# LinuxBoard_v1_2.net
KiCad netlist of a schematic drawn in EAGLE
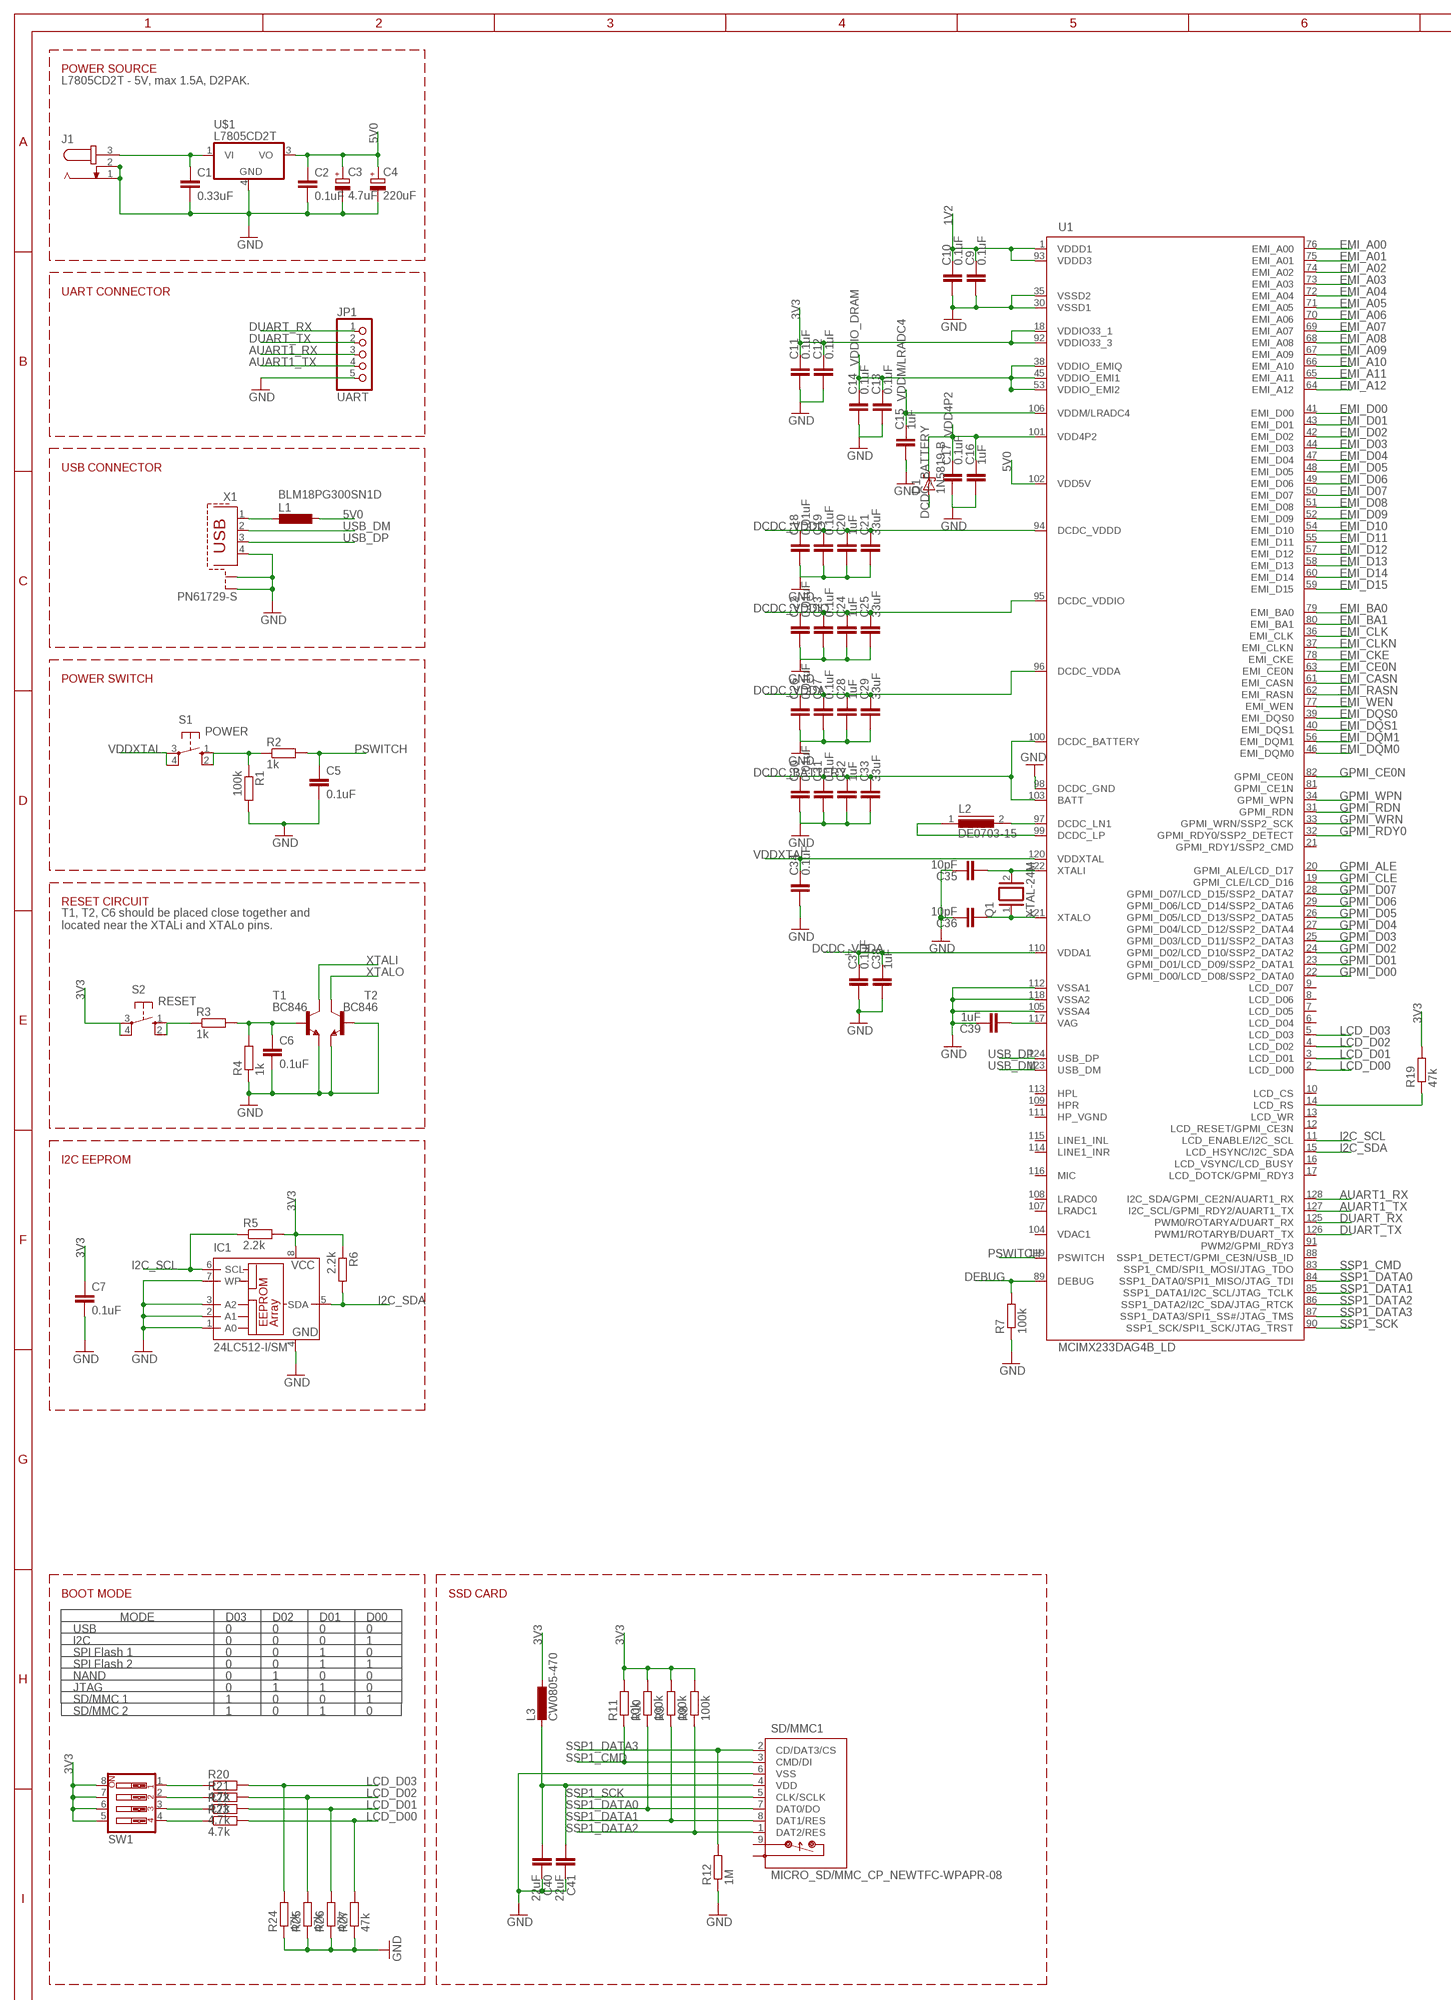
[diagram p0: schematic, sheet 1, part 1 of 2]
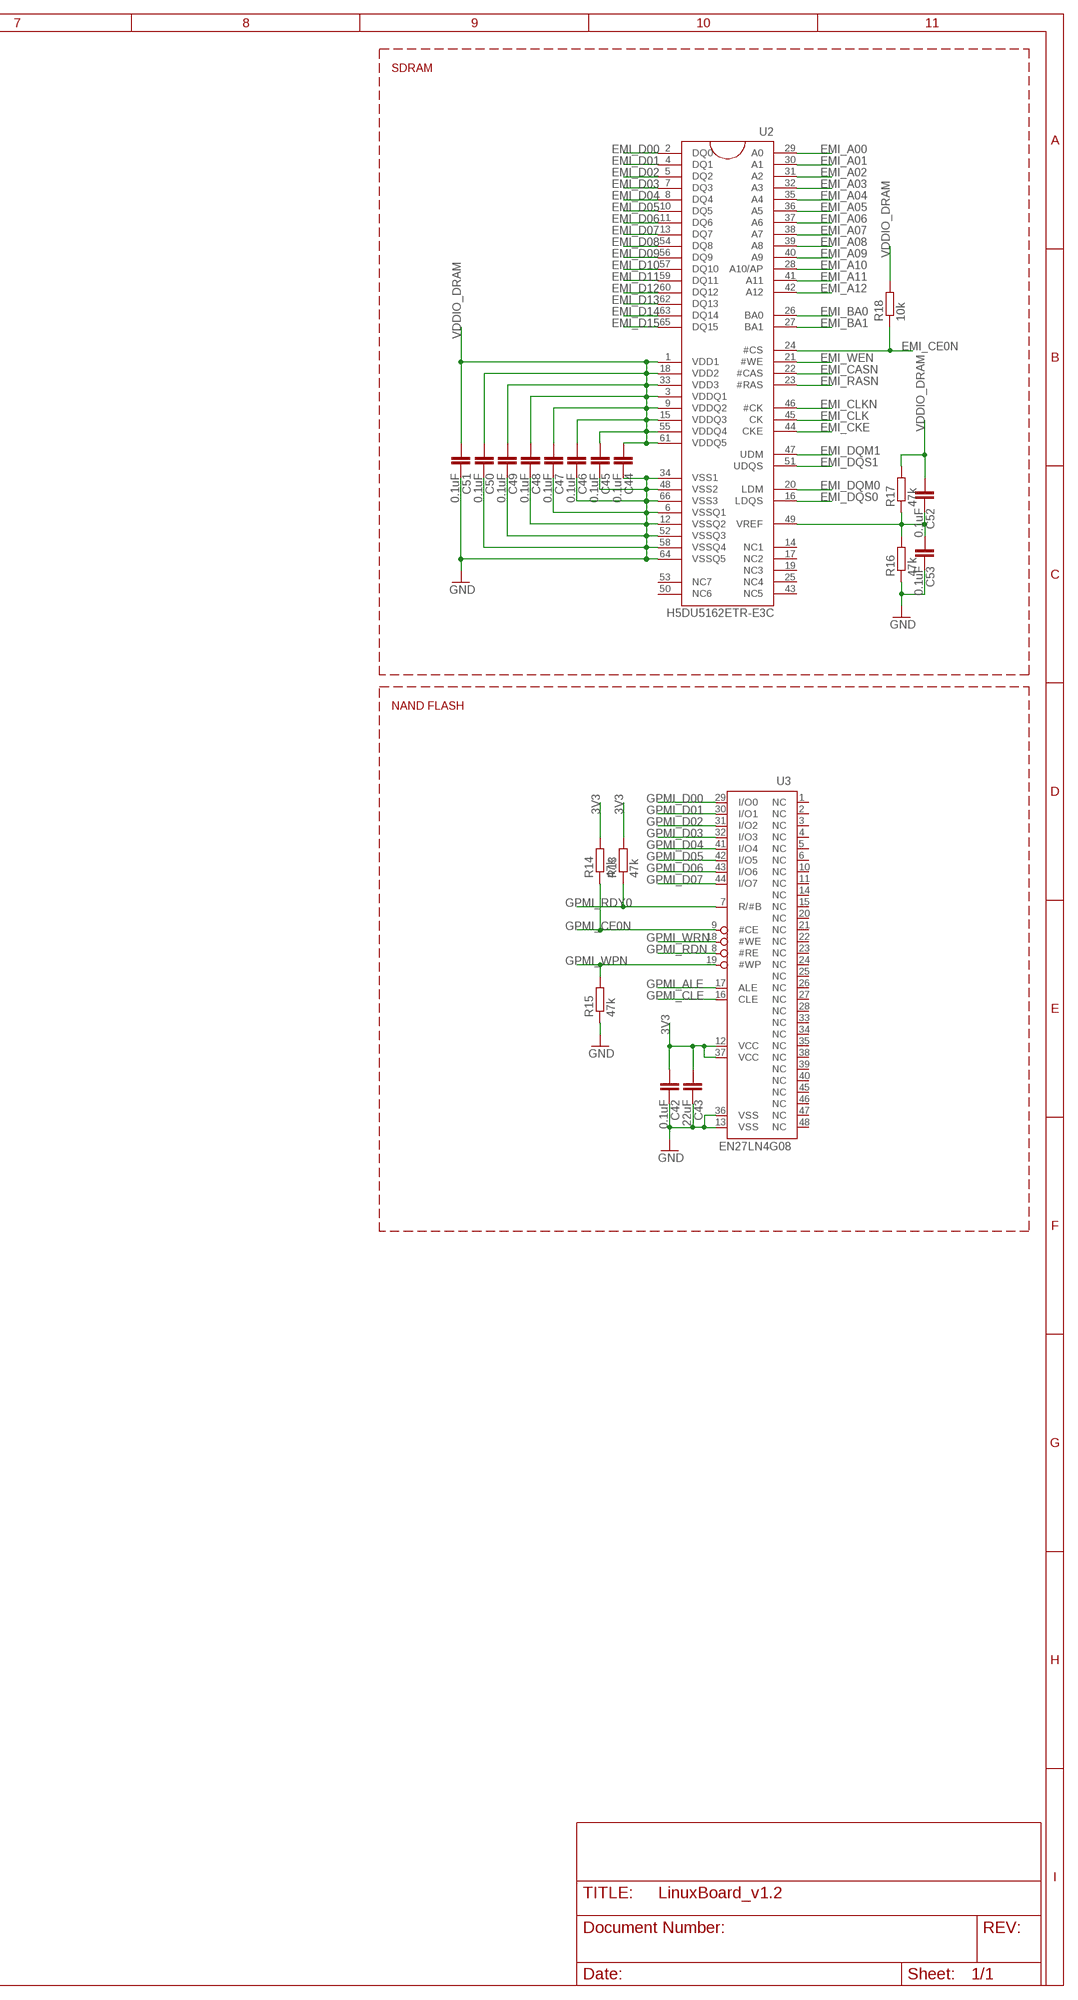
[diagram p1: schematic, sheet 1, part 2 of 2]

(export (version "E")
  (design (tool "Eeschema 10.0.6"))
  (components
    (comp (ref "C1")
      (value "0.33uF")
      (footprint "eagle-import:C0805")
      (libsource (lib "eagle-import") (part "C-EUC0805"))
    )
    (comp (ref "C2")
      (value "0.1uF")
      (footprint "eagle-import:C0805")
      (libsource (lib "eagle-import") (part "C-EUC0805"))
    )
    (comp (ref "C3")
      (value "4.7uF")
      (footprint "eagle-import:E2-5")
      (libsource (lib "eagle-import") (part "CPOL-EUE2-5"))
    )
    (comp (ref "C4")
      (value "220uF")
      (footprint "eagle-import:E2-5")
      (libsource (lib "eagle-import") (part "CPOL-EUE2-5"))
    )
    (comp (ref "C5")
      (value "0.1uF")
      (footprint "eagle-import:C0805")
      (libsource (lib "eagle-import") (part "C-EUC0805"))
    )
    (comp (ref "C6")
      (value "0.1uF")
      (footprint "eagle-import:C0805")
      (libsource (lib "eagle-import") (part "C-EUC0805"))
    )
    (comp (ref "C7")
      (value "0.1uF")
      (footprint "eagle-import:C0805")
      (libsource (lib "eagle-import") (part "C-EUC0805"))
    )
    (comp (ref "C9")
      (value "0.1uF")
      (footprint "eagle-import:C0805")
      (libsource (lib "eagle-import") (part "C-EUC0805"))
    )
    (comp (ref "C10")
      (value "0.1uF")
      (footprint "eagle-import:C0805")
      (libsource (lib "eagle-import") (part "C-EUC0805"))
    )
    (comp (ref "C11")
      (value "0.1uF")
      (footprint "eagle-import:C0805")
      (libsource (lib "eagle-import") (part "C-EUC0805"))
    )
    (comp (ref "C12")
      (value "0.1uF")
      (footprint "eagle-import:C0805")
      (libsource (lib "eagle-import") (part "C-EUC0805"))
    )
    (comp (ref "C13")
      (value "0.1uF")
      (footprint "eagle-import:C0805")
      (libsource (lib "eagle-import") (part "C-EUC0805"))
    )
    (comp (ref "C14")
      (value "0.1uF")
      (footprint "eagle-import:C0805")
      (libsource (lib "eagle-import") (part "C-EUC0805"))
    )
    (comp (ref "C15")
      (value "1uF")
      (footprint "eagle-import:C0805")
      (libsource (lib "eagle-import") (part "C-EUC0805"))
    )
    (comp (ref "C16")
      (value "1uF")
      (footprint "eagle-import:C0805")
      (libsource (lib "eagle-import") (part "C-EUC0805"))
    )
    (comp (ref "C17")
      (value "0.1uF")
      (footprint "eagle-import:C0805")
      (libsource (lib "eagle-import") (part "C-EUC0805"))
    )
    (comp (ref "C18")
      (value "0.01uF")
      (footprint "eagle-import:C0805")
      (libsource (lib "eagle-import") (part "C-EUC0805"))
    )
    (comp (ref "C19")
      (value "0.1uF")
      (footprint "eagle-import:C0805")
      (libsource (lib "eagle-import") (part "C-EUC0805"))
    )
    (comp (ref "C20")
      (value "1uF")
      (footprint "eagle-import:C0805")
      (libsource (lib "eagle-import") (part "C-EUC0805"))
    )
    (comp (ref "C21")
      (value "33uF")
      (footprint "eagle-import:C0805")
      (libsource (lib "eagle-import") (part "C-EUC0805"))
    )
    (comp (ref "C22")
      (value "0.01uF")
      (footprint "eagle-import:C0805")
      (libsource (lib "eagle-import") (part "C-EUC0805"))
    )
    (comp (ref "C23")
      (value "0.1uF")
      (footprint "eagle-import:C0805")
      (libsource (lib "eagle-import") (part "C-EUC0805"))
    )
    (comp (ref "C24")
      (value "1uF")
      (footprint "eagle-import:C0805")
      (libsource (lib "eagle-import") (part "C-EUC0805"))
    )
    (comp (ref "C25")
      (value "33uF")
      (footprint "eagle-import:C0805")
      (libsource (lib "eagle-import") (part "C-EUC0805"))
    )
    (comp (ref "C26")
      (value "0.01uF")
      (footprint "eagle-import:C0805")
      (libsource (lib "eagle-import") (part "C-EUC0805"))
    )
    (comp (ref "C27")
      (value "0.1uF")
      (footprint "eagle-import:C0805")
      (libsource (lib "eagle-import") (part "C-EUC0805"))
    )
    (comp (ref "C28")
      (value "1uF")
      (footprint "eagle-import:C0805")
      (libsource (lib "eagle-import") (part "C-EUC0805"))
    )
    (comp (ref "C29")
      (value "33uF")
      (footprint "eagle-import:C0805")
      (libsource (lib "eagle-import") (part "C-EUC0805"))
    )
    (comp (ref "C30")
      (value "0.01uF")
      (footprint "eagle-import:C0805")
      (libsource (lib "eagle-import") (part "C-EUC0805"))
    )
    (comp (ref "C31")
      (value "0.1uF")
      (footprint "eagle-import:C0805")
      (libsource (lib "eagle-import") (part "C-EUC0805"))
    )
    (comp (ref "C32")
      (value "1uF")
      (footprint "eagle-import:C0805")
      (libsource (lib "eagle-import") (part "C-EUC0805"))
    )
    (comp (ref "C33")
      (value "33uF")
      (footprint "eagle-import:C0805")
      (libsource (lib "eagle-import") (part "C-EUC0805"))
    )
    (comp (ref "C34")
      (value "0.1uF")
      (footprint "eagle-import:C0805")
      (libsource (lib "eagle-import") (part "C-EUC0805"))
    )
    (comp (ref "C35")
      (value "10pF")
      (footprint "eagle-import:C0805")
      (libsource (lib "eagle-import") (part "C-EUC0805"))
    )
    (comp (ref "C36")
      (value "10pF")
      (footprint "eagle-import:C0805")
      (libsource (lib "eagle-import") (part "C-EUC0805"))
    )
    (comp (ref "C37")
      (value "0.1uF")
      (footprint "eagle-import:C0805")
      (libsource (lib "eagle-import") (part "C-EUC0805"))
    )
    (comp (ref "C38")
      (value "1uF")
      (footprint "eagle-import:C0805")
      (libsource (lib "eagle-import") (part "C-EUC0805"))
    )
    (comp (ref "C39")
      (value "1uF")
      (footprint "eagle-import:C0805")
      (libsource (lib "eagle-import") (part "C-EUC0805"))
    )
    (comp (ref "C40")
      (value "22uF")
      (footprint "eagle-import:C0805")
      (libsource (lib "eagle-import") (part "C-EUC0805"))
    )
    (comp (ref "C41")
      (value "22uF")
      (footprint "eagle-import:C0805")
      (libsource (lib "eagle-import") (part "C-EUC0805"))
    )
    (comp (ref "C42")
      (value "0.1uF")
      (footprint "eagle-import:C0805")
      (libsource (lib "eagle-import") (part "C-EUC0805"))
    )
    (comp (ref "C43")
      (value "22uF")
      (footprint "eagle-import:C0805")
      (libsource (lib "eagle-import") (part "C-EUC0805"))
    )
    (comp (ref "C44")
      (value "0.1uF")
      (footprint "eagle-import:C0805")
      (libsource (lib "eagle-import") (part "C-EUC0805"))
    )
    (comp (ref "C45")
      (value "0.1uF")
      (footprint "eagle-import:C0805")
      (libsource (lib "eagle-import") (part "C-EUC0805"))
    )
    (comp (ref "C46")
      (value "0.1uF")
      (footprint "eagle-import:C0805")
      (libsource (lib "eagle-import") (part "C-EUC0805"))
    )
    (comp (ref "C47")
      (value "0.1uF")
      (footprint "eagle-import:C0805")
      (libsource (lib "eagle-import") (part "C-EUC0805"))
    )
    (comp (ref "C48")
      (value "0.1uF")
      (footprint "eagle-import:C0805")
      (libsource (lib "eagle-import") (part "C-EUC0805"))
    )
    (comp (ref "C49")
      (value "0.1uF")
      (footprint "eagle-import:C0805")
      (libsource (lib "eagle-import") (part "C-EUC0805"))
    )
    (comp (ref "C50")
      (value "0.1uF")
      (footprint "eagle-import:C0805")
      (libsource (lib "eagle-import") (part "C-EUC0805"))
    )
    (comp (ref "C51")
      (value "0.1uF")
      (footprint "eagle-import:C0805")
      (libsource (lib "eagle-import") (part "C-EUC0805"))
    )
    (comp (ref "C52")
      (value "0.1uF")
      (footprint "eagle-import:C0805")
      (libsource (lib "eagle-import") (part "C-EUC0805"))
    )
    (comp (ref "C53")
      (value "0.1uF")
      (footprint "eagle-import:C0805")
      (libsource (lib "eagle-import") (part "C-EUC0805"))
    )
    (comp (ref "D1")
      (value "1N5819-B")
      (footprint "eagle-import:DO41-7.6")
      (libsource (lib "eagle-import") (part "1N5819-B"))
    )
    (comp (ref "IC1")
      (value "24LC512-I/SM")
      (footprint "eagle-import:SO-08")
      (fields (field (name "MF") "MICROCHIP") (field (name "MPN") "24LC128-I/SNG"))
      (libsource (lib "eagle-import") (part "24SNLC128"))
    )
    (comp (ref "J1")
      (value "JACK-PLUG0")
      (footprint "eagle-import:SPC4077")
      (libsource (lib "eagle-import") (part "JACK-PLUG0"))
    )
    (comp (ref "JP1")
      (value "UART")
      (footprint "eagle-import:1X05")
      (libsource (lib "eagle-import") (part "PINHD-1X5"))
    )
    (comp (ref "L1")
      (value "BLM18PG300SN1D")
      (footprint "eagle-import:L0201")
      (libsource (lib "eagle-import") (part "L-EUL0201"))
    )
    (comp (ref "L2")
      (value "DE0703-15")
      (footprint "eagle-import:DR73")
      (libsource (lib "eagle-import") (part "DR73"))
    )
    (comp (ref "L3")
      (value "CW0805-470")
      (footprint "eagle-import:L2012C")
      (libsource (lib "eagle-import") (part "L-EUL2012C"))
    )
    (comp (ref "Q1")
      (value "XTAL-24M")
      (footprint "eagle-import:QS")
      (libsource (lib "eagle-import") (part "XTAL/S"))
    )
    (comp (ref "R1")
      (value "100k")
      (footprint "eagle-import:R0805")
      (libsource (lib "eagle-import") (part "R-EU_R0805"))
    )
    (comp (ref "R2")
      (value "1k")
      (footprint "eagle-import:R0805")
      (libsource (lib "eagle-import") (part "R-EU_R0805"))
    )
    (comp (ref "R3")
      (value "1k")
      (footprint "eagle-import:R0805")
      (libsource (lib "eagle-import") (part "R-EU_R0805"))
    )
    (comp (ref "R4")
      (value "1k")
      (footprint "eagle-import:R0805")
      (libsource (lib "eagle-import") (part "R-EU_R0805"))
    )
    (comp (ref "R5")
      (value "2.2k")
      (footprint "eagle-import:R0805")
      (libsource (lib "eagle-import") (part "R-EU_R0805"))
    )
    (comp (ref "R6")
      (value "2.2k")
      (footprint "eagle-import:R0805")
      (libsource (lib "eagle-import") (part "R-EU_R0805"))
    )
    (comp (ref "R7")
      (value "100k")
      (footprint "eagle-import:R0805")
      (libsource (lib "eagle-import") (part "R-EU_R0805"))
    )
    (comp (ref "R8")
      (value "100k")
      (footprint "eagle-import:R0805")
      (libsource (lib "eagle-import") (part "R-EU_R0805"))
    )
    (comp (ref "R9")
      (value "100k")
      (footprint "eagle-import:R0805")
      (libsource (lib "eagle-import") (part "R-EU_R0805"))
    )
    (comp (ref "R10")
      (value "100k")
      (footprint "eagle-import:R0805")
      (libsource (lib "eagle-import") (part "R-EU_R0805"))
    )
    (comp (ref "R11")
      (value "10k")
      (footprint "eagle-import:R0805")
      (libsource (lib "eagle-import") (part "R-EU_R0805"))
    )
    (comp (ref "R12")
      (value "1M")
      (footprint "eagle-import:R0805")
      (libsource (lib "eagle-import") (part "R-EU_R0805"))
    )
    (comp (ref "R13")
      (value "47k")
      (footprint "eagle-import:R0805")
      (libsource (lib "eagle-import") (part "R-EU_R0805"))
    )
    (comp (ref "R14")
      (value "47k")
      (footprint "eagle-import:R0805")
      (libsource (lib "eagle-import") (part "R-EU_R0805"))
    )
    (comp (ref "R15")
      (value "47k")
      (footprint "eagle-import:R0805")
      (libsource (lib "eagle-import") (part "R-EU_R0805"))
    )
    (comp (ref "R16")
      (value "47k")
      (footprint "eagle-import:R0805")
      (libsource (lib "eagle-import") (part "R-EU_R0805"))
    )
    (comp (ref "R17")
      (value "47k")
      (footprint "eagle-import:R0805")
      (libsource (lib "eagle-import") (part "R-EU_R0805"))
    )
    (comp (ref "R18")
      (value "10k")
      (footprint "eagle-import:R0805")
      (libsource (lib "eagle-import") (part "R-EU_R0805"))
    )
    (comp (ref "R19")
      (value "47k")
      (footprint "eagle-import:R0805")
      (libsource (lib "eagle-import") (part "R-EU_R0805"))
    )
    (comp (ref "R20")
      (value "4.7k")
      (footprint "eagle-import:R0805")
      (libsource (lib "eagle-import") (part "R-EU_R0805"))
    )
    (comp (ref "R21")
      (value "4.7k")
      (footprint "eagle-import:R0805")
      (libsource (lib "eagle-import") (part "R-EU_R0805"))
    )
    (comp (ref "R22")
      (value "4.7k")
      (footprint "eagle-import:R0805")
      (libsource (lib "eagle-import") (part "R-EU_R0805"))
    )
    (comp (ref "R23")
      (value "4.7k")
      (footprint "eagle-import:R0805")
      (libsource (lib "eagle-import") (part "R-EU_R0805"))
    )
    (comp (ref "R24")
      (value "47k")
      (footprint "eagle-import:R0805")
      (libsource (lib "eagle-import") (part "R-EU_R0805"))
    )
    (comp (ref "R25")
      (value "47k")
      (footprint "eagle-import:R0805")
      (libsource (lib "eagle-import") (part "R-EU_R0805"))
    )
    (comp (ref "R26")
      (value "47k")
      (footprint "eagle-import:R0805")
      (libsource (lib "eagle-import") (part "R-EU_R0805"))
    )
    (comp (ref "R27")
      (value "47k")
      (footprint "eagle-import:R0805")
      (libsource (lib "eagle-import") (part "R-EU_R0805"))
    )
    (comp (ref "S1")
      (value "POWER")
      (footprint "eagle-import:B3F-10XX")
      (fields (field (name "MPN") "B3F-1000"))
      (libsource (lib "eagle-import") (part "10-XX"))
    )
    (comp (ref "S2")
      (value "RESET")
      (footprint "eagle-import:B3F-10XX")
      (fields (field (name "MPN") "B3F-1000"))
      (libsource (lib "eagle-import") (part "10-XX"))
    )
    (comp (ref "SD/MMC1")
      (value "MICRO_SD/MMC_CP_NEWTFC-WPAPR-08")
      (footprint "eagle-import:TFC-WPAPR-08")
      (libsource (lib "eagle-import") (part "MICRO_SD/MMC_CP_NEWTFC-WPAPR-08"))
    )
    (comp (ref "SW1")
      (value "SW_DIP-4")
      (footprint "eagle-import:EDG-04")
      (libsource (lib "eagle-import") (part "SW_DIP-4"))
    )
    (comp (ref "T1")
      (value "BC846")
      (footprint "eagle-import:SOT23")
      (libsource (lib "eagle-import") (part "BC846"))
    )
    (comp (ref "T2")
      (value "BC846")
      (footprint "eagle-import:SOT23")
      (libsource (lib "eagle-import") (part "BC846"))
    )
    (comp (ref "U$1")
      (value "L7805CD2T")
      (footprint "eagle-import:D2PAK-3")
      (libsource (lib "eagle-import") (part "L7805CD2T"))
    )
    (comp (ref "U1")
      (value "MCIMX233DAG4B_LD")
      (footprint "eagle-import:TQFP128LD")
      (libsource (lib "eagle-import") (part "MCIMX233DAG4B_LD"))
    )
    (comp (ref "U2")
      (value "H5DU5162ETR-E3C")
      (footprint "eagle-import:66TSOP-II")
      (libsource (lib "eagle-import") (part "HY5DU121622D(L)T(P)-J"))
    )
    (comp (ref "U3")
      (value "EN27LN4G08")
      (footprint "eagle-import:TSOP48")
      (libsource (lib "eagle-import") (part "H27UBG8T2A"))
    )
    (comp (ref "X1")
      (value "PN61729-S")
      (footprint "eagle-import:PN61729-S")
      (libsource (lib "eagle-import") (part "PN61729-S"))
    )
  )
  (nets
    (net (code "1") (name "/1V2") (class "Default")
      (node (ref "C10") (pin "1") (pinfunction "1_1") (pintype "passive"))
      (node (ref "C9") (pin "1") (pinfunction "1_1") (pintype "passive"))
      (node (ref "U1") (pin "1") (pinfunction "VDDD1_1") (pintype "power_in"))
      (node (ref "U1") (pin "93") (pinfunction "VDDD3_93") (pintype "power_in"))
    )
    (net (code "2") (name "/3V3") (class "Default")
      (node (ref "C11") (pin "1") (pinfunction "1_1") (pintype "passive"))
      (node (ref "C12") (pin "1") (pinfunction "1_1") (pintype "passive"))
      (node (ref "C42") (pin "2") (pinfunction "2_2") (pintype "passive"))
      (node (ref "C43") (pin "2") (pinfunction "2_2") (pintype "passive"))
      (node (ref "C7") (pin "1") (pinfunction "1_1") (pintype "passive"))
      (node (ref "IC1") (pin "8") (pinfunction "VCC_8") (pintype "power_in"))
      (node (ref "L3") (pin "1") (pinfunction "1_1") (pintype "passive"))
      (node (ref "R10") (pin "2") (pinfunction "2_2") (pintype "passive"))
      (node (ref "R11") (pin "2") (pinfunction "2_2") (pintype "passive"))
      (node (ref "R13") (pin "2") (pinfunction "2_2") (pintype "passive"))
      (node (ref "R14") (pin "2") (pinfunction "2_2") (pintype "passive"))
      (node (ref "R19") (pin "2") (pinfunction "2_2") (pintype "passive"))
      (node (ref "R5") (pin "2") (pinfunction "2_2") (pintype "passive"))
      (node (ref "R6") (pin "1") (pinfunction "1_1") (pintype "passive"))
      (node (ref "R8") (pin "2") (pinfunction "2_2") (pintype "passive"))
      (node (ref "R9") (pin "2") (pinfunction "2_2") (pintype "passive"))
      (node (ref "S2") (pin "3") (pinfunction "P_3") (pintype "passive"))
      (node (ref "S2") (pin "4") (pinfunction "P1_4") (pintype "passive"))
      (node (ref "SW1") (pin "5") (pinfunction "5_5") (pintype "passive"))
      (node (ref "SW1") (pin "6") (pinfunction "6_6") (pintype "passive"))
      (node (ref "SW1") (pin "7") (pinfunction "7_7") (pintype "passive"))
      (node (ref "SW1") (pin "8") (pinfunction "8_8") (pintype "passive"))
      (node (ref "U1") (pin "18") (pinfunction "VDDIO33_1_18") (pintype "power_in"))
      (node (ref "U1") (pin "92") (pinfunction "VDDIO33_3_92") (pintype "power_in"))
      (node (ref "U3") (pin "12") (pinfunction "VCC_12") (pintype "power_in"))
      (node (ref "U3") (pin "37") (pinfunction "VCC_37") (pintype "power_in"))
    )
    (net (code "3") (name "/5V0") (class "Default")
      (node (ref "C2") (pin "1") (pinfunction "1_1") (pintype "passive"))
      (node (ref "C3") (pin "+") (pinfunction "+_+") (pintype "passive"))
      (node (ref "C4") (pin "+") (pinfunction "+_+") (pintype "passive"))
      (node (ref "L1") (pin "1") (pinfunction "1_1") (pintype "passive"))
      (node (ref "U$1") (pin "3") (pinfunction "VO_3") (pintype "passive"))
      (node (ref "U1") (pin "102") (pinfunction "VDD5V_102") (pintype "power_in"))
    )
    (net (code "4") (name "/AUART1_RX") (class "Default")
      (node (ref "JP1") (pin "3") (pinfunction "3_3") (pintype "passive"))
      (node (ref "U1") (pin "128") (pinfunction "I2C_SDA/GPMI_CE2N/AUART1_RX_128") (pintype "bidirectional"))
    )
    (net (code "5") (name "/AUART1_TX") (class "Default")
      (node (ref "JP1") (pin "4") (pinfunction "4_4") (pintype "passive"))
      (node (ref "U1") (pin "127") (pinfunction "I2C_SCL/GPMI_RDY2/AUART1_TX_127") (pintype "bidirectional"))
    )
    (net (code "6") (name "/DCDC_BATTERY") (class "Default")
      (node (ref "C30") (pin "1") (pinfunction "1_1") (pintype "passive"))
      (node (ref "C31") (pin "1") (pinfunction "1_1") (pintype "passive"))
      (node (ref "C32") (pin "1") (pinfunction "1_1") (pintype "passive"))
      (node (ref "C33") (pin "1") (pinfunction "1_1") (pintype "passive"))
      (node (ref "D1") (pin "A") (pinfunction "A_A") (pintype "passive"))
      (node (ref "U1") (pin "100") (pinfunction "DCDC_BATTERY_100") (pintype "power_in"))
      (node (ref "U1") (pin "103") (pinfunction "BATT_103") (pintype "input"))
    )
    (net (code "7") (name "/DCDC_VDDA") (class "Default")
      (node (ref "C26") (pin "1") (pinfunction "1_1") (pintype "passive"))
      (node (ref "C27") (pin "1") (pinfunction "1_1") (pintype "passive"))
      (node (ref "C28") (pin "1") (pinfunction "1_1") (pintype "passive"))
      (node (ref "C29") (pin "1") (pinfunction "1_1") (pintype "passive"))
      (node (ref "C37") (pin "1") (pinfunction "1_1") (pintype "passive"))
      (node (ref "C38") (pin "1") (pinfunction "1_1") (pintype "passive"))
      (node (ref "U1") (pin "110") (pinfunction "VDDA1_110") (pintype "power_in"))
      (node (ref "U1") (pin "96") (pinfunction "DCDC_VDDA_96") (pintype "power_in"))
    )
    (net (code "8") (name "/DCDC_VDDD") (class "Default")
      (node (ref "C18") (pin "1") (pinfunction "1_1") (pintype "passive"))
      (node (ref "C19") (pin "1") (pinfunction "1_1") (pintype "passive"))
      (node (ref "C20") (pin "1") (pinfunction "1_1") (pintype "passive"))
      (node (ref "C21") (pin "1") (pinfunction "1_1") (pintype "passive"))
      (node (ref "U1") (pin "94") (pinfunction "DCDC_VDDD_94") (pintype "power_in"))
    )
    (net (code "9") (name "/DCDC_VDDIO") (class "Default")
      (node (ref "C22") (pin "1") (pinfunction "1_1") (pintype "passive"))
      (node (ref "C23") (pin "1") (pinfunction "1_1") (pintype "passive"))
      (node (ref "C24") (pin "1") (pinfunction "1_1") (pintype "passive"))
      (node (ref "C25") (pin "1") (pinfunction "1_1") (pintype "passive"))
      (node (ref "U1") (pin "95") (pinfunction "DCDC_VDDIO_95") (pintype "power_in"))
    )
    (net (code "10") (name "/DEBUG") (class "Default")
      (node (ref "R7") (pin "2") (pinfunction "2_2") (pintype "passive"))
      (node (ref "U1") (pin "89") (pinfunction "DEBUG_89") (pintype "bidirectional"))
    )
    (net (code "11") (name "/DUART_RX") (class "Default")
      (node (ref "JP1") (pin "1") (pinfunction "1_1") (pintype "passive"))
      (node (ref "U1") (pin "125") (pinfunction "PWM0/ROTARYA/DUART_RX_125") (pintype "bidirectional"))
    )
    (net (code "12") (name "/DUART_TX") (class "Default")
      (node (ref "JP1") (pin "2") (pinfunction "2_2") (pintype "passive"))
      (node (ref "U1") (pin "126") (pinfunction "PWM1/ROTARYB/DUART_TX_126") (pintype "bidirectional"))
    )
    (net (code "13") (name "/EMI_A00") (class "Default")
      (node (ref "U1") (pin "76") (pinfunction "EMI_A00_76") (pintype "bidirectional"))
      (node (ref "U2") (pin "29") (pinfunction "A0_29") (pintype "input"))
    )
    (net (code "14") (name "/EMI_A01") (class "Default")
      (node (ref "U1") (pin "75") (pinfunction "EMI_A01_75") (pintype "bidirectional"))
      (node (ref "U2") (pin "30") (pinfunction "A1_30") (pintype "input"))
    )
    (net (code "15") (name "/EMI_A02") (class "Default")
      (node (ref "U1") (pin "74") (pinfunction "EMI_A02_74") (pintype "bidirectional"))
      (node (ref "U2") (pin "31") (pinfunction "A2_31") (pintype "input"))
    )
    (net (code "16") (name "/EMI_A03") (class "Default")
      (node (ref "U1") (pin "73") (pinfunction "EMI_A03_73") (pintype "bidirectional"))
      (node (ref "U2") (pin "32") (pinfunction "A3_32") (pintype "input"))
    )
    (net (code "17") (name "/EMI_A04") (class "Default")
      (node (ref "U1") (pin "72") (pinfunction "EMI_A04_72") (pintype "bidirectional"))
      (node (ref "U2") (pin "35") (pinfunction "A4_35") (pintype "input"))
    )
    (net (code "18") (name "/EMI_A05") (class "Default")
      (node (ref "U1") (pin "71") (pinfunction "EMI_A05_71") (pintype "bidirectional"))
      (node (ref "U2") (pin "36") (pinfunction "A5_36") (pintype "input"))
    )
    (net (code "19") (name "/EMI_A06") (class "Default")
      (node (ref "U1") (pin "70") (pinfunction "EMI_A06_70") (pintype "bidirectional"))
      (node (ref "U2") (pin "37") (pinfunction "A6_37") (pintype "input"))
    )
    (net (code "20") (name "/EMI_A07") (class "Default")
      (node (ref "U1") (pin "69") (pinfunction "EMI_A07_69") (pintype "bidirectional"))
      (node (ref "U2") (pin "38") (pinfunction "A7_38") (pintype "input"))
    )
    (net (code "21") (name "/EMI_A08") (class "Default")
      (node (ref "U1") (pin "68") (pinfunction "EMI_A08_68") (pintype "bidirectional"))
      (node (ref "U2") (pin "39") (pinfunction "A8_39") (pintype "input"))
    )
    (net (code "22") (name "/EMI_A09") (class "Default")
      (node (ref "U1") (pin "67") (pinfunction "EMI_A09_67") (pintype "bidirectional"))
      (node (ref "U2") (pin "40") (pinfunction "A9_40") (pintype "input"))
    )
    (net (code "23") (name "/EMI_A10") (class "Default")
      (node (ref "U1") (pin "66") (pinfunction "EMI_A10_66") (pintype "bidirectional"))
      (node (ref "U2") (pin "28") (pinfunction "A10/AP_28") (pintype "input"))
    )
    (net (code "24") (name "/EMI_A11") (class "Default")
      (node (ref "U1") (pin "65") (pinfunction "EMI_A11_65") (pintype "bidirectional"))
      (node (ref "U2") (pin "41") (pinfunction "A11_41") (pintype "input"))
    )
    (net (code "25") (name "/EMI_A12") (class "Default")
      (node (ref "U1") (pin "64") (pinfunction "EMI_A12_64") (pintype "bidirectional"))
      (node (ref "U2") (pin "42") (pinfunction "A12_42") (pintype "input"))
    )
    (net (code "26") (name "/EMI_BA0") (class "Default")
      (node (ref "U1") (pin "79") (pinfunction "EMI_BA0_79") (pintype "output"))
      (node (ref "U2") (pin "26") (pinfunction "BA0_26") (pintype "input"))
    )
    (net (code "27") (name "/EMI_BA1") (class "Default")
      (node (ref "U1") (pin "80") (pinfunction "EMI_BA1_80") (pintype "output"))
      (node (ref "U2") (pin "27") (pinfunction "BA1_27") (pintype "input"))
    )
    (net (code "28") (name "/EMI_CASN") (class "Default")
      (node (ref "U1") (pin "61") (pinfunction "EMI_CASN_61") (pintype "output"))
      (node (ref "U2") (pin "22") (pinfunction "#CAS_22") (pintype "input"))
    )
    (net (code "29") (name "/EMI_CE0N") (class "Default")
      (node (ref "R18") (pin "1") (pinfunction "1_1") (pintype "passive"))
      (node (ref "U1") (pin "63") (pinfunction "EMI_CE0N_63") (pintype "output"))
      (node (ref "U2") (pin "24") (pinfunction "#CS_24") (pintype "input"))
    )
    (net (code "30") (name "/EMI_CKE") (class "Default")
      (node (ref "U1") (pin "78") (pinfunction "EMI_CKE_78") (pintype "output"))
      (node (ref "U2") (pin "44") (pinfunction "CKE_44") (pintype "input"))
    )
    (net (code "31") (name "/EMI_CLK") (class "Default")
      (node (ref "U1") (pin "36") (pinfunction "EMI_CLK_36") (pintype "output"))
      (node (ref "U2") (pin "45") (pinfunction "CK_45") (pintype "input"))
    )
    (net (code "32") (name "/EMI_CLKN") (class "Default")
      (node (ref "U1") (pin "37") (pinfunction "EMI_CLKN_37") (pintype "output"))
      (node (ref "U2") (pin "46") (pinfunction "#CK_46") (pintype "input"))
    )
    (net (code "33") (name "/EMI_D00") (class "Default")
      (node (ref "U1") (pin "41") (pinfunction "EMI_D00_41") (pintype "bidirectional"))
      (node (ref "U2") (pin "2") (pinfunction "DQ0_2") (pintype "bidirectional"))
    )
    (net (code "34") (name "/EMI_D01") (class "Default")
      (node (ref "U1") (pin "43") (pinfunction "EMI_D01_43") (pintype "bidirectional"))
      (node (ref "U2") (pin "4") (pinfunction "DQ1_4") (pintype "bidirectional"))
    )
    (net (code "35") (name "/EMI_D02") (class "Default")
      (node (ref "U1") (pin "42") (pinfunction "EMI_D02_42") (pintype "bidirectional"))
      (node (ref "U2") (pin "5") (pinfunction "DQ2_5") (pintype "bidirectional"))
    )
    (net (code "36") (name "/EMI_D03") (class "Default")
      (node (ref "U1") (pin "44") (pinfunction "EMI_D03_44") (pintype "bidirectional"))
      (node (ref "U2") (pin "7") (pinfunction "DQ3_7") (pintype "bidirectional"))
    )
    (net (code "37") (name "/EMI_D04") (class "Default")
      (node (ref "U1") (pin "47") (pinfunction "EMI_D04_47") (pintype "bidirectional"))
      (node (ref "U2") (pin "8") (pinfunction "DQ4_8") (pintype "bidirectional"))
    )
    (net (code "38") (name "/EMI_D05") (class "Default")
      (node (ref "U1") (pin "48") (pinfunction "EMI_D05_48") (pintype "bidirectional"))
      (node (ref "U2") (pin "10") (pinfunction "DQ5_10") (pintype "bidirectional"))
    )
    (net (code "39") (name "/EMI_D06") (class "Default")
      (node (ref "U1") (pin "49") (pinfunction "EMI_D06_49") (pintype "bidirectional"))
      (node (ref "U2") (pin "11") (pinfunction "DQ6_11") (pintype "bidirectional"))
    )
    (net (code "40") (name "/EMI_D07") (class "Default")
      (node (ref "U1") (pin "50") (pinfunction "EMI_D07_50") (pintype "bidirectional"))
      (node (ref "U2") (pin "13") (pinfunction "DQ7_13") (pintype "bidirectional"))
    )
    (net (code "41") (name "/EMI_D08") (class "Default")
      (node (ref "U1") (pin "51") (pinfunction "EMI_D08_51") (pintype "bidirectional"))
      (node (ref "U2") (pin "54") (pinfunction "DQ8_54") (pintype "bidirectional"))
    )
    (net (code "42") (name "/EMI_D09") (class "Default")
      (node (ref "U1") (pin "52") (pinfunction "EMI_D09_52") (pintype "bidirectional"))
      (node (ref "U2") (pin "56") (pinfunction "DQ9_56") (pintype "bidirectional"))
    )
    (net (code "43") (name "/EMI_D10") (class "Default")
      (node (ref "U1") (pin "54") (pinfunction "EMI_D10_54") (pintype "bidirectional"))
      (node (ref "U2") (pin "57") (pinfunction "DQ10_57") (pintype "bidirectional"))
    )
    (net (code "44") (name "/EMI_D11") (class "Default")
      (node (ref "U1") (pin "55") (pinfunction "EMI_D11_55") (pintype "bidirectional"))
      (node (ref "U2") (pin "59") (pinfunction "DQ11_59") (pintype "bidirectional"))
    )
    (net (code "45") (name "/EMI_D12") (class "Default")
      (node (ref "U1") (pin "57") (pinfunction "EMI_D12_57") (pintype "bidirectional"))
      (node (ref "U2") (pin "60") (pinfunction "DQ12_60") (pintype "bidirectional"))
    )
    (net (code "46") (name "/EMI_D13") (class "Default")
      (node (ref "U1") (pin "58") (pinfunction "EMI_D13_58") (pintype "bidirectional"))
      (node (ref "U2") (pin "62") (pinfunction "DQ13_62") (pintype "bidirectional"))
    )
    (net (code "47") (name "/EMI_D14") (class "Default")
      (node (ref "U1") (pin "60") (pinfunction "EMI_D14_60") (pintype "bidirectional"))
      (node (ref "U2") (pin "63") (pinfunction "DQ14_63") (pintype "bidirectional"))
    )
    (net (code "48") (name "/EMI_D15") (class "Default")
      (node (ref "U1") (pin "59") (pinfunction "EMI_D15_59") (pintype "bidirectional"))
      (node (ref "U2") (pin "65") (pinfunction "DQ15_65") (pintype "bidirectional"))
    )
    (net (code "49") (name "/EMI_DQM0") (class "Default")
      (node (ref "U1") (pin "46") (pinfunction "EMI_DQM0_46") (pintype "output"))
      (node (ref "U2") (pin "20") (pinfunction "LDM_20") (pintype "input"))
    )
    (net (code "50") (name "/EMI_DQM1") (class "Default")
      (node (ref "U1") (pin "56") (pinfunction "EMI_DQM1_56") (pintype "output"))
      (node (ref "U2") (pin "47") (pinfunction "UDM_47") (pintype "input"))
    )
    (net (code "51") (name "/EMI_DQS0") (class "Default")
      (node (ref "U1") (pin "39") (pinfunction "EMI_DQS0_39") (pintype "output"))
      (node (ref "U2") (pin "16") (pinfunction "LDQS_16") (pintype "bidirectional"))
    )
    (net (code "52") (name "/EMI_DQS1") (class "Default")
      (node (ref "U1") (pin "40") (pinfunction "EMI_DQS1_40") (pintype "output"))
      (node (ref "U2") (pin "51") (pinfunction "UDQS_51") (pintype "input"))
    )
    (net (code "53") (name "/EMI_RASN") (class "Default")
      (node (ref "U1") (pin "62") (pinfunction "EMI_RASN_62") (pintype "output"))
      (node (ref "U2") (pin "23") (pinfunction "#RAS_23") (pintype "input"))
    )
    (net (code "54") (name "/EMI_WEN") (class "Default")
      (node (ref "U1") (pin "77") (pinfunction "EMI_WEN_77") (pintype "output"))
      (node (ref "U2") (pin "21") (pinfunction "#WE_21") (pintype "input"))
    )
    (net (code "55") (name "/GPMI_ALE") (class "Default")
      (node (ref "U1") (pin "20") (pinfunction "GPMI_ALE/LCD_D17_20") (pintype "bidirectional"))
      (node (ref "U3") (pin "17") (pinfunction "ALE_17") (pintype "input"))
    )
    (net (code "56") (name "/GPMI_CE0N") (class "Default")
      (node (ref "R14") (pin "1") (pinfunction "1_1") (pintype "passive"))
      (node (ref "U1") (pin "82") (pinfunction "GPMI_CE0N_82") (pintype "bidirectional"))
      (node (ref "U3") (pin "9") (pinfunction "#CE_9") (pintype "input"))
    )
    (net (code "57") (name "/GPMI_CLE") (class "Default")
      (node (ref "U1") (pin "19") (pinfunction "GPMI_CLE/LCD_D16_19") (pintype "bidirectional"))
      (node (ref "U3") (pin "16") (pinfunction "CLE_16") (pintype "input"))
    )
    (net (code "58") (name "/GPMI_D00") (class "Default")
      (node (ref "U1") (pin "22") (pinfunction "GPMI_D00/LCD_D08/SSP2_DATA0_22") (pintype "bidirectional"))
      (node (ref "U3") (pin "29") (pinfunction "I/O0_29") (pintype "bidirectional"))
    )
    (net (code "59") (name "/GPMI_D01") (class "Default")
      (node (ref "U1") (pin "23") (pinfunction "GPMI_D01/LCD_D09/SSP2_DATA1_23") (pintype "bidirectional"))
      (node (ref "U3") (pin "30") (pinfunction "I/O1_30") (pintype "bidirectional"))
    )
    (net (code "60") (name "/GPMI_D02") (class "Default")
      (node (ref "U1") (pin "24") (pinfunction "GPMI_D02/LCD_D10/SSP2_DATA2_24") (pintype "bidirectional"))
      (node (ref "U3") (pin "31") (pinfunction "I/O2_31") (pintype "bidirectional"))
    )
    (net (code "61") (name "/GPMI_D03") (class "Default")
      (node (ref "U1") (pin "25") (pinfunction "GPMI_D03/LCD_D11/SSP2_DATA3_25") (pintype "bidirectional"))
      (node (ref "U3") (pin "32") (pinfunction "I/O3_32") (pintype "bidirectional"))
    )
    (net (code "62") (name "/GPMI_D04") (class "Default")
      (node (ref "U1") (pin "27") (pinfunction "GPMI_D04/LCD_D12/SSP2_DATA4_27") (pintype "bidirectional"))
      (node (ref "U3") (pin "41") (pinfunction "I/O4_41") (pintype "bidirectional"))
    )
    (net (code "63") (name "/GPMI_D05") (class "Default")
      (node (ref "U1") (pin "26") (pinfunction "GPMI_D05/LCD_D13/SSP2_DATA5_26") (pintype "bidirectional"))
      (node (ref "U3") (pin "42") (pinfunction "I/O5_42") (pintype "bidirectional"))
    )
    (net (code "64") (name "/GPMI_D06") (class "Default")
      (node (ref "U1") (pin "29") (pinfunction "GPMI_D06/LCD_D14/SSP2_DATA6_29") (pintype "bidirectional"))
      (node (ref "U3") (pin "43") (pinfunction "I/O6_43") (pintype "bidirectional"))
    )
    (net (code "65") (name "/GPMI_D07") (class "Default")
      (node (ref "U1") (pin "28") (pinfunction "GPMI_D07/LCD_D15/SSP2_DATA7_28") (pintype "bidirectional"))
      (node (ref "U3") (pin "44") (pinfunction "I/O7_44") (pintype "bidirectional"))
    )
    (net (code "66") (name "/GPMI_RDN") (class "Default")
      (node (ref "U1") (pin "31") (pinfunction "GPMI_RDN_31") (pintype "bidirectional"))
      (node (ref "U3") (pin "8") (pinfunction "#RE_8") (pintype "input"))
    )
    (net (code "67") (name "/GPMI_RDY0") (class "Default")
      (node (ref "R13") (pin "1") (pinfunction "1_1") (pintype "passive"))
      (node (ref "U1") (pin "32") (pinfunction "GPMI_RDY0/SSP2_DETECT_32") (pintype "bidirectional"))
      (node (ref "U3") (pin "7") (pinfunction "R/#B_7") (pintype "output"))
    )
    (net (code "68") (name "/GPMI_WPN") (class "Default")
      (node (ref "R15") (pin "2") (pinfunction "2_2") (pintype "passive"))
      (node (ref "U1") (pin "34") (pinfunction "GPMI_WPN_34") (pintype "bidirectional"))
      (node (ref "U3") (pin "19") (pinfunction "#WP_19") (pintype "input"))
    )
    (net (code "69") (name "/GPMI_WRN") (class "Default")
      (node (ref "U1") (pin "33") (pinfunction "GPMI_WRN/SSP2_SCK_33") (pintype "bidirectional"))
      (node (ref "U3") (pin "18") (pinfunction "#WE_18") (pintype "input"))
    )
    (net (code "70") (name "/HP_VGND") (class "Default")
      (node (ref "U1") (pin "111") (pinfunction "HP_VGND_111") (pintype "power_in"))
    )
    (net (code "71") (name "/I2C_SCL") (class "Default")
      (node (ref "IC1") (pin "6") (pinfunction "SCL_6") (pintype "input"))
      (node (ref "R5") (pin "1") (pinfunction "1_1") (pintype "passive"))
      (node (ref "U1") (pin "11") (pinfunction "LCD_ENABLE/I2C_SCL_11") (pintype "bidirectional"))
    )
    (net (code "72") (name "/I2C_SDA") (class "Default")
      (node (ref "IC1") (pin "5") (pinfunction "SDA_5") (pintype "bidirectional"))
      (node (ref "R6") (pin "2") (pinfunction "2_2") (pintype "passive"))
      (node (ref "U1") (pin "15") (pinfunction "LCD_HSYNC/I2C_SDA_15") (pintype "bidirectional"))
    )
    (net (code "73") (name "/LCD_D00") (class "Default")
      (node (ref "R23") (pin "2") (pinfunction "2_2") (pintype "passive"))
      (node (ref "R27") (pin "2") (pinfunction "2_2") (pintype "passive"))
      (node (ref "U1") (pin "2") (pinfunction "LCD_D00_2") (pintype "bidirectional"))
    )
    (net (code "74") (name "/LCD_D01") (class "Default")
      (node (ref "R22") (pin "2") (pinfunction "2_2") (pintype "passive"))
      (node (ref "R26") (pin "2") (pinfunction "2_2") (pintype "passive"))
      (node (ref "U1") (pin "3") (pinfunction "LCD_D01_3") (pintype "bidirectional"))
    )
    (net (code "75") (name "/LCD_D02") (class "Default")
      (node (ref "R21") (pin "2") (pinfunction "2_2") (pintype "passive"))
      (node (ref "R25") (pin "2") (pinfunction "2_2") (pintype "passive"))
      (node (ref "U1") (pin "4") (pinfunction "LCD_D02_4") (pintype "bidirectional"))
    )
    (net (code "76") (name "/LCD_D03") (class "Default")
      (node (ref "R20") (pin "2") (pinfunction "2_2") (pintype "passive"))
      (node (ref "R24") (pin "2") (pinfunction "2_2") (pintype "passive"))
      (node (ref "U1") (pin "5") (pinfunction "LCD_D03_5") (pintype "bidirectional"))
    )
    (net (code "77") (name "/PSWITCH") (class "Default")
      (node (ref "C5") (pin "1") (pinfunction "1_1") (pintype "passive"))
      (node (ref "R2") (pin "2") (pinfunction "2_2") (pintype "passive"))
      (node (ref "U1") (pin "119") (pinfunction "PSWITCH_119") (pintype "input"))
    )
    (net (code "78") (name "/SSP1_CMD") (class "Default")
      (node (ref "R11") (pin "1") (pinfunction "1_1") (pintype "passive"))
      (node (ref "SD/MMC1") (pin "3") (pinfunction "CMD/DI_3") (pintype "input"))
      (node (ref "U1") (pin "83") (pinfunction "SSP1_CMD/SPI1_MOSI/JTAG_TDO_83") (pintype "bidirectional"))
    )
    (net (code "79") (name "/SSP1_DATA0") (class "Default")
      (node (ref "R10") (pin "1") (pinfunction "1_1") (pintype "passive"))
      (node (ref "SD/MMC1") (pin "7") (pinfunction "DAT0/DO_7") (pintype "output"))
      (node (ref "U1") (pin "84") (pinfunction "SSP1_DATA0/SPI1_MISO/JTAG_TDI_84") (pintype "bidirectional"))
    )
    (net (code "80") (name "/SSP1_DATA1") (class "Default")
      (node (ref "R9") (pin "1") (pinfunction "1_1") (pintype "passive"))
      (node (ref "SD/MMC1") (pin "8") (pinfunction "DAT1/RES_8") (pintype "bidirectional"))
      (node (ref "U1") (pin "85") (pinfunction "SSP1_DATA1/I2C_SCL/JTAG_TCLK_85") (pintype "bidirectional"))
    )
    (net (code "81") (name "/SSP1_DATA2") (class "Default")
      (node (ref "R8") (pin "1") (pinfunction "1_1") (pintype "passive"))
      (node (ref "SD/MMC1") (pin "1") (pinfunction "DAT2/RES_1") (pintype "bidirectional"))
      (node (ref "U1") (pin "86") (pinfunction "SSP1_DATA2/I2C_SDA/JTAG_RTCK_86") (pintype "bidirectional"))
    )
    (net (code "82") (name "/SSP1_DATA3") (class "Default")
      (node (ref "R12") (pin "2") (pinfunction "2_2") (pintype "passive"))
      (node (ref "SD/MMC1") (pin "2") (pinfunction "CD/DAT3/CS_2") (pintype "input"))
      (node (ref "U1") (pin "87") (pinfunction "SSP1_DATA3/SPI1_SS#/JTAG_TMS_87") (pintype "bidirectional"))
    )
    (net (code "83") (name "/SSP1_SCK") (class "Default")
      (node (ref "SD/MMC1") (pin "5") (pinfunction "CLK/SCLK_5") (pintype "input"))
      (node (ref "U1") (pin "90") (pinfunction "SSP1_SCK/SPI1_SCK/JTAG_TRST_90") (pintype "bidirectional"))
    )
    (net (code "84") (name "/USB_DM") (class "Default")
      (node (ref "U1") (pin "123") (pinfunction "USB_DM_123") (pintype "bidirectional"))
      (node (ref "X1") (pin "2") (pinfunction "2_2") (pintype "passive"))
    )
    (net (code "85") (name "/USB_DP") (class "Default")
      (node (ref "U1") (pin "124") (pinfunction "USB_DP_124") (pintype "bidirectional"))
      (node (ref "X1") (pin "3") (pinfunction "3_3") (pintype "passive"))
    )
    (net (code "86") (name "/VDD4P2") (class "Default")
      (node (ref "C16") (pin "1") (pinfunction "1_1") (pintype "passive"))
      (node (ref "C17") (pin "1") (pinfunction "1_1") (pintype "passive"))
      (node (ref "D1") (pin "C") (pinfunction "C_C") (pintype "passive"))
      (node (ref "U1") (pin "101") (pinfunction "VDD4P2_101") (pintype "power_in"))
    )
    (net (code "87") (name "/VDDIO_DRAM") (class "Default")
      (node (ref "C13") (pin "1") (pinfunction "1_1") (pintype "passive"))
      (node (ref "C14") (pin "1") (pinfunction "1_1") (pintype "passive"))
      (node (ref "C44") (pin "2") (pinfunction "2_2") (pintype "passive"))
      (node (ref "C45") (pin "2") (pinfunction "2_2") (pintype "passive"))
      (node (ref "C46") (pin "2") (pinfunction "2_2") (pintype "passive"))
      (node (ref "C47") (pin "2") (pinfunction "2_2") (pintype "passive"))
      (node (ref "C48") (pin "2") (pinfunction "2_2") (pintype "passive"))
      (node (ref "C49") (pin "2") (pinfunction "2_2") (pintype "passive"))
      (node (ref "C50") (pin "2") (pinfunction "2_2") (pintype "passive"))
      (node (ref "C51") (pin "2") (pinfunction "2_2") (pintype "passive"))
      (node (ref "C52") (pin "2") (pinfunction "2_2") (pintype "passive"))
      (node (ref "R17") (pin "2") (pinfunction "2_2") (pintype "passive"))
      (node (ref "R18") (pin "2") (pinfunction "2_2") (pintype "passive"))
      (node (ref "U1") (pin "38") (pinfunction "VDDIO_EMIQ_38") (pintype "power_in"))
      (node (ref "U1") (pin "45") (pinfunction "VDDIO_EMI1_45") (pintype "power_in"))
      (node (ref "U1") (pin "53") (pinfunction "VDDIO_EMI2_53") (pintype "power_in"))
      (node (ref "U2") (pin "1") (pinfunction "VDD1_1") (pintype "power_in"))
      (node (ref "U2") (pin "15") (pinfunction "VDDQ3_15") (pintype "power_in"))
      (node (ref "U2") (pin "18") (pinfunction "VDD2_18") (pintype "power_in"))
      (node (ref "U2") (pin "3") (pinfunction "VDDQ1_3") (pintype "power_in"))
      (node (ref "U2") (pin "33") (pinfunction "VDD3_33") (pintype "power_in"))
      (node (ref "U2") (pin "55") (pinfunction "VDDQ4_55") (pintype "power_in"))
      (node (ref "U2") (pin "61") (pinfunction "VDDQ5_61") (pintype "power_in"))
      (node (ref "U2") (pin "9") (pinfunction "VDDQ2_9") (pintype "power_in"))
    )
    (net (code "88") (name "/VDDM{slash}LRADC4") (class "Default")
      (node (ref "C15") (pin "1") (pinfunction "1_1") (pintype "passive"))
      (node (ref "U1") (pin "106") (pinfunction "VDDM/LRADC4_106") (pintype "power_in"))
    )
    (net (code "89") (name "/VDDXTAL") (class "Default")
      (node (ref "C34") (pin "1") (pinfunction "1_1") (pintype "passive"))
      (node (ref "S1") (pin "3") (pinfunction "P_3") (pintype "passive"))
      (node (ref "S1") (pin "4") (pinfunction "P1_4") (pintype "passive"))
      (node (ref "U1") (pin "120") (pinfunction "VDDXTAL_120") (pintype "passive"))
    )
    (net (code "90") (name "/XTALI") (class "Default")
      (node (ref "C35") (pin "2") (pinfunction "2_2") (pintype "passive"))
      (node (ref "Q1") (pin "2") (pinfunction "2_2") (pintype "passive"))
      (node (ref "T1") (pin "3") (pinfunction "C_3") (pintype "passive"))
      (node (ref "U1") (pin "122") (pinfunction "XTALI_122") (pintype "input"))
    )
    (net (code "91") (name "/XTALO") (class "Default")
      (node (ref "C36") (pin "2") (pinfunction "2_2") (pintype "passive"))
      (node (ref "Q1") (pin "1") (pinfunction "1_1") (pintype "passive"))
      (node (ref "T2") (pin "3") (pinfunction "C_3") (pintype "passive"))
      (node (ref "U1") (pin "121") (pinfunction "XTALO_121") (pintype "output"))
    )
    (net (code "92") (name "GND") (class "Default")
      (node (ref "C1") (pin "2") (pinfunction "2_2") (pintype "passive"))
      (node (ref "C10") (pin "2") (pinfunction "2_2") (pintype "passive"))
      (node (ref "C11") (pin "2") (pinfunction "2_2") (pintype "passive"))
      (node (ref "C12") (pin "2") (pinfunction "2_2") (pintype "passive"))
      (node (ref "C13") (pin "2") (pinfunction "2_2") (pintype "passive"))
      (node (ref "C14") (pin "2") (pinfunction "2_2") (pintype "passive"))
      (node (ref "C15") (pin "2") (pinfunction "2_2") (pintype "passive"))
      (node (ref "C16") (pin "2") (pinfunction "2_2") (pintype "passive"))
      (node (ref "C17") (pin "2") (pinfunction "2_2") (pintype "passive"))
      (node (ref "C18") (pin "2") (pinfunction "2_2") (pintype "passive"))
      (node (ref "C19") (pin "2") (pinfunction "2_2") (pintype "passive"))
      (node (ref "C2") (pin "2") (pinfunction "2_2") (pintype "passive"))
      (node (ref "C20") (pin "2") (pinfunction "2_2") (pintype "passive"))
      (node (ref "C21") (pin "2") (pinfunction "2_2") (pintype "passive"))
      (node (ref "C22") (pin "2") (pinfunction "2_2") (pintype "passive"))
      (node (ref "C23") (pin "2") (pinfunction "2_2") (pintype "passive"))
      (node (ref "C24") (pin "2") (pinfunction "2_2") (pintype "passive"))
      (node (ref "C25") (pin "2") (pinfunction "2_2") (pintype "passive"))
      (node (ref "C26") (pin "2") (pinfunction "2_2") (pintype "passive"))
      (node (ref "C27") (pin "2") (pinfunction "2_2") (pintype "passive"))
      (node (ref "C28") (pin "2") (pinfunction "2_2") (pintype "passive"))
      (node (ref "C29") (pin "2") (pinfunction "2_2") (pintype "passive"))
      (node (ref "C3") (pin "-") (pinfunction "-_-") (pintype "passive"))
      (node (ref "C30") (pin "2") (pinfunction "2_2") (pintype "passive"))
      (node (ref "C31") (pin "2") (pinfunction "2_2") (pintype "passive"))
      (node (ref "C32") (pin "2") (pinfunction "2_2") (pintype "passive"))
      (node (ref "C33") (pin "2") (pinfunction "2_2") (pintype "passive"))
      (node (ref "C34") (pin "2") (pinfunction "2_2") (pintype "passive"))
      (node (ref "C35") (pin "1") (pinfunction "1_1") (pintype "passive"))
      (node (ref "C36") (pin "1") (pinfunction "1_1") (pintype "passive"))
      (node (ref "C37") (pin "2") (pinfunction "2_2") (pintype "passive"))
      (node (ref "C38") (pin "2") (pinfunction "2_2") (pintype "passive"))
      (node (ref "C39") (pin "1") (pinfunction "1_1") (pintype "passive"))
      (node (ref "C4") (pin "-") (pinfunction "-_-") (pintype "passive"))
      (node (ref "C40") (pin "1") (pinfunction "1_1") (pintype "passive"))
      (node (ref "C41") (pin "1") (pinfunction "1_1") (pintype "passive"))
      (node (ref "C42") (pin "1") (pinfunction "1_1") (pintype "passive"))
      (node (ref "C43") (pin "1") (pinfunction "1_1") (pintype "passive"))
      (node (ref "C44") (pin "1") (pinfunction "1_1") (pintype "passive"))
      (node (ref "C45") (pin "1") (pinfunction "1_1") (pintype "passive"))
      (node (ref "C46") (pin "1") (pinfunction "1_1") (pintype "passive"))
      (node (ref "C47") (pin "1") (pinfunction "1_1") (pintype "passive"))
      (node (ref "C48") (pin "1") (pinfunction "1_1") (pintype "passive"))
      (node (ref "C49") (pin "1") (pinfunction "1_1") (pintype "passive"))
      (node (ref "C5") (pin "2") (pinfunction "2_2") (pintype "passive"))
      (node (ref "C50") (pin "1") (pinfunction "1_1") (pintype "passive"))
      (node (ref "C51") (pin "1") (pinfunction "1_1") (pintype "passive"))
      (node (ref "C53") (pin "1") (pinfunction "1_1") (pintype "passive"))
      (node (ref "C6") (pin "2") (pinfunction "2_2") (pintype "passive"))
      (node (ref "C7") (pin "2") (pinfunction "2_2") (pintype "passive"))
      (node (ref "C9") (pin "2") (pinfunction "2_2") (pintype "passive"))
      (node (ref "IC1") (pin "1") (pinfunction "A0_1") (pintype "input"))
      (node (ref "IC1") (pin "2") (pinfunction "A1_2") (pintype "input"))
      (node (ref "IC1") (pin "3") (pinfunction "A2_3") (pintype "input"))
      (node (ref "IC1") (pin "4") (pinfunction "GND_4") (pintype "power_in"))
      (node (ref "IC1") (pin "7") (pinfunction "WP_7") (pintype "input"))
      (node (ref "J1") (pin "1") (pinfunction "1_1") (pintype "passive"))
      (node (ref "J1") (pin "2") (pinfunction "2_2") (pintype "passive"))
      (node (ref "JP1") (pin "5") (pinfunction "5_5") (pintype "passive"))
      (node (ref "R1") (pin "2") (pinfunction "2_2") (pintype "passive"))
      (node (ref "R12") (pin "1") (pinfunction "1_1") (pintype "passive"))
      (node (ref "R15") (pin "1") (pinfunction "1_1") (pintype "passive"))
      (node (ref "R16") (pin "1") (pinfunction "1_1") (pintype "passive"))
      (node (ref "R24") (pin "1") (pinfunction "1_1") (pintype "passive"))
      (node (ref "R25") (pin "1") (pinfunction "1_1") (pintype "passive"))
      (node (ref "R26") (pin "1") (pinfunction "1_1") (pintype "passive"))
      (node (ref "R27") (pin "1") (pinfunction "1_1") (pintype "passive"))
      (node (ref "R4") (pin "1") (pinfunction "1_1") (pintype "passive"))
      (node (ref "R7") (pin "1") (pinfunction "1_1") (pintype "passive"))
      (node (ref "SD/MMC1") (pin "6") (pinfunction "VSS_6") (pintype "power_in"))
      (node (ref "T1") (pin "2") (pinfunction "E_2") (pintype "passive"))
      (node (ref "T2") (pin "1") (pinfunction "B_1") (pintype "passive"))
      (node (ref "T2") (pin "2") (pinfunction "E_2") (pintype "passive"))
      (node (ref "U$1") (pin "4") (pinfunction "GND_4") (pintype "passive"))
      (node (ref "U1") (pin "105") (pinfunction "VSSA4_105") (pintype "power_in"))
      (node (ref "U1") (pin "112") (pinfunction "VSSA1_112") (pintype "power_in"))
      (node (ref "U1") (pin "118") (pinfunction "VSSA2_118") (pintype "power_in"))
      (node (ref "U1") (pin "30") (pinfunction "VSSD1_30") (pintype "power_in"))
      (node (ref "U1") (pin "35") (pinfunction "VSSD2_35") (pintype "power_in"))
      (node (ref "U1") (pin "98") (pinfunction "DCDC_GND_98") (pintype "power_in"))
      (node (ref "U2") (pin "12") (pinfunction "VSSQ2_12") (pintype "power_in"))
      (node (ref "U2") (pin "34") (pinfunction "VSS1_34") (pintype "power_in"))
      (node (ref "U2") (pin "48") (pinfunction "VSS2_48") (pintype "power_in"))
      (node (ref "U2") (pin "52") (pinfunction "VSSQ3_52") (pintype "power_in"))
      (node (ref "U2") (pin "58") (pinfunction "VSSQ4_58") (pintype "power_in"))
      (node (ref "U2") (pin "6") (pinfunction "VSSQ1_6") (pintype "power_in"))
      (node (ref "U2") (pin "64") (pinfunction "VSSQ5_64") (pintype "power_in"))
      (node (ref "U2") (pin "66") (pinfunction "VSS3_66") (pintype "power_in"))
      (node (ref "U3") (pin "13") (pinfunction "VSS_13") (pintype "power_in"))
      (node (ref "U3") (pin "36") (pinfunction "VSS_36") (pintype "power_in"))
      (node (ref "X1") (pin "4") (pinfunction "4_4") (pintype "passive"))
      (node (ref "X1") (pin "S1") (pinfunction "S1_S1") (pintype "passive"))
      (node (ref "X1") (pin "S2") (pinfunction "S2_S2") (pintype "passive"))
    )
    (net (code "93") (name "Net-(L1-Pad2)") (class "Default")
      (node (ref "L1") (pin "2") (pinfunction "2_2") (pintype "passive"))
      (node (ref "X1") (pin "1") (pinfunction "1_1") (pintype "passive"))
    )
    (net (code "94") (name "Net-(R20-Pad1)") (class "Default")
      (node (ref "R20") (pin "1") (pinfunction "1_1") (pintype "passive"))
      (node (ref "SW1") (pin "1") (pinfunction "1_1") (pintype "passive"))
    )
    (net (code "95") (name "Net-(R21-Pad1)") (class "Default")
      (node (ref "R21") (pin "1") (pinfunction "1_1") (pintype "passive"))
      (node (ref "SW1") (pin "2") (pinfunction "2_2") (pintype "passive"))
    )
    (net (code "96") (name "Net-(R22-Pad1)") (class "Default")
      (node (ref "R22") (pin "1") (pinfunction "1_1") (pintype "passive"))
      (node (ref "SW1") (pin "3") (pinfunction "3_3") (pintype "passive"))
    )
    (net (code "97") (name "Net-(R23-Pad1)") (class "Default")
      (node (ref "R23") (pin "1") (pinfunction "1_1") (pintype "passive"))
      (node (ref "SW1") (pin "4") (pinfunction "4_4") (pintype "passive"))
    )
    (net (code "98") (name "Net-(S1-S)") (class "Default")
      (node (ref "R1") (pin "1") (pinfunction "1_1") (pintype "passive"))
      (node (ref "R2") (pin "1") (pinfunction "1_1") (pintype "passive"))
      (node (ref "S1") (pin "1") (pinfunction "S_1") (pintype "passive"))
      (node (ref "S1") (pin "2") (pinfunction "S1_2") (pintype "passive"))
    )
    (net (code "99") (name "Net-(S2-S)") (class "Default")
      (node (ref "R3") (pin "1") (pinfunction "1_1") (pintype "passive"))
      (node (ref "S2") (pin "1") (pinfunction "S_1") (pintype "passive"))
      (node (ref "S2") (pin "2") (pinfunction "S1_2") (pintype "passive"))
    )
    (net (code "100") (name "Net-(SD/MMC1-VDD)") (class "Default")
      (node (ref "C40") (pin "2") (pinfunction "2_2") (pintype "passive"))
      (node (ref "C41") (pin "2") (pinfunction "2_2") (pintype "passive"))
      (node (ref "L3") (pin "2") (pinfunction "2_2") (pintype "passive"))
      (node (ref "SD/MMC1") (pin "4") (pinfunction "VDD_4") (pintype "power_in"))
    )
    (net (code "101") (name "Net-(T1-B)") (class "Default")
      (node (ref "C6") (pin "1") (pinfunction "1_1") (pintype "passive"))
      (node (ref "R3") (pin "2") (pinfunction "2_2") (pintype "passive"))
      (node (ref "R4") (pin "2") (pinfunction "2_2") (pintype "passive"))
      (node (ref "T1") (pin "1") (pinfunction "B_1") (pintype "passive"))
    )
    (net (code "102") (name "Net-(U$1-VI)") (class "Default")
      (node (ref "C1") (pin "1") (pinfunction "1_1") (pintype "passive"))
      (node (ref "J1") (pin "3") (pinfunction "3_3") (pintype "passive"))
      (node (ref "U$1") (pin "1") (pinfunction "VI_1") (pintype "input"))
    )
    (net (code "103") (name "Net-(U1-DCDC_LN1)") (class "Default")
      (node (ref "L2") (pin "2") (pinfunction "2_2") (pintype "passive"))
      (node (ref "U1") (pin "97") (pinfunction "DCDC_LN1_97") (pintype "passive"))
    )
    (net (code "104") (name "Net-(U1-DCDC_LP)") (class "Default")
      (node (ref "L2") (pin "1") (pinfunction "1_1") (pintype "passive"))
      (node (ref "U1") (pin "99") (pinfunction "DCDC_LP_99") (pintype "passive"))
    )
    (net (code "105") (name "Net-(U1-LCD_RS)") (class "Default")
      (node (ref "R19") (pin "1") (pinfunction "1_1") (pintype "passive"))
      (node (ref "U1") (pin "14") (pinfunction "LCD_RS_14") (pintype "bidirectional"))
    )
    (net (code "106") (name "Net-(U1-VAG)") (class "Default")
      (node (ref "C39") (pin "2") (pinfunction "2_2") (pintype "passive"))
      (node (ref "U1") (pin "117") (pinfunction "VAG_117") (pintype "passive"))
    )
    (net (code "107") (name "Net-(U2-VREF)") (class "Default")
      (node (ref "C52") (pin "1") (pinfunction "1_1") (pintype "passive"))
      (node (ref "C53") (pin "2") (pinfunction "2_2") (pintype "passive"))
      (node (ref "R16") (pin "2") (pinfunction "2_2") (pintype "passive"))
      (node (ref "R17") (pin "1") (pinfunction "1_1") (pintype "passive"))
      (node (ref "U2") (pin "49") (pinfunction "VREF_49") (pintype "input"))
    )
    (net (code "108") (name "unconnected-(SD/MMC1-CP_E-Pad9)") (class "Default")
      (node (ref "SD/MMC1") (pin "9") (pinfunction "CP_E_9") (pintype "input"))
    )
    (net (code "109") (name "unconnected-(SD/MMC1-PACK1-Pad10)") (class "Default")
      (node (ref "SD/MMC1") (pin "10") (pinfunction "PACK1_10") (pintype "input"))
    )
    (net (code "110") (name "unconnected-(U1-GPMI_CE1N-Pad81)") (class "Default")
      (node (ref "U1") (pin "81") (pinfunction "GPMI_CE1N_81") (pintype "bidirectional"))
    )
    (net (code "111") (name "unconnected-(U1-GPMI_RDY1{slash}SSP2_CMD-Pad21)") (class "Default")
      (node (ref "U1") (pin "21") (pinfunction "GPMI_RDY1/SSP2_CMD_21") (pintype "bidirectional"))
    )
    (net (code "112") (name "unconnected-(U1-HPL-Pad113)") (class "Default")
      (node (ref "U1") (pin "113") (pinfunction "HPL_113") (pintype "output"))
    )
    (net (code "113") (name "unconnected-(U1-HPR-Pad109)") (class "Default")
      (node (ref "U1") (pin "109") (pinfunction "HPR_109") (pintype "output"))
    )
    (net (code "114") (name "unconnected-(U1-LCD_CS-Pad10)") (class "Default")
      (node (ref "U1") (pin "10") (pinfunction "LCD_CS_10") (pintype "bidirectional"))
    )
    (net (code "115") (name "unconnected-(U1-LCD_D04-Pad6)") (class "Default")
      (node (ref "U1") (pin "6") (pinfunction "LCD_D04_6") (pintype "bidirectional"))
    )
    (net (code "116") (name "unconnected-(U1-LCD_D05-Pad7)") (class "Default")
      (node (ref "U1") (pin "7") (pinfunction "LCD_D05_7") (pintype "bidirectional"))
    )
    (net (code "117") (name "unconnected-(U1-LCD_D06-Pad8)") (class "Default")
      (node (ref "U1") (pin "8") (pinfunction "LCD_D06_8") (pintype "bidirectional"))
    )
    (net (code "118") (name "unconnected-(U1-LCD_D07-Pad9)") (class "Default")
      (node (ref "U1") (pin "9") (pinfunction "LCD_D07_9") (pintype "bidirectional"))
    )
    (net (code "119") (name "unconnected-(U1-LCD_DOTCK{slash}GPMI_RDY3-Pad17)") (class "Default")
      (node (ref "U1") (pin "17") (pinfunction "LCD_DOTCK/GPMI_RDY3_17") (pintype "bidirectional"))
    )
    (net (code "120") (name "unconnected-(U1-LCD_RESET{slash}GPMI_CE3N-Pad12)") (class "Default")
      (node (ref "U1") (pin "12") (pinfunction "LCD_RESET/GPMI_CE3N_12") (pintype "bidirectional"))
    )
    (net (code "121") (name "unconnected-(U1-LCD_VSYNC{slash}LCD_BUSY-Pad16)") (class "Default")
      (node (ref "U1") (pin "16") (pinfunction "LCD_VSYNC/LCD_BUSY_16") (pintype "bidirectional"))
    )
    (net (code "122") (name "unconnected-(U1-LCD_WR-Pad13)") (class "Default")
      (node (ref "U1") (pin "13") (pinfunction "LCD_WR_13") (pintype "bidirectional"))
    )
    (net (code "123") (name "unconnected-(U1-LINE1_INL-Pad115)") (class "Default")
      (node (ref "U1") (pin "115") (pinfunction "LINE1_INL_115") (pintype "input"))
    )
    (net (code "124") (name "unconnected-(U1-LINE1_INR-Pad114)") (class "Default")
      (node (ref "U1") (pin "114") (pinfunction "LINE1_INR_114") (pintype "input"))
    )
    (net (code "125") (name "unconnected-(U1-LRADC0-Pad108)") (class "Default")
      (node (ref "U1") (pin "108") (pinfunction "LRADC0_108") (pintype "bidirectional"))
    )
    (net (code "126") (name "unconnected-(U1-LRADC1-Pad107)") (class "Default")
      (node (ref "U1") (pin "107") (pinfunction "LRADC1_107") (pintype "bidirectional"))
    )
    (net (code "127") (name "unconnected-(U1-MIC-Pad116)") (class "Default")
      (node (ref "U1") (pin "116") (pinfunction "MIC_116") (pintype "input"))
    )
    (net (code "128") (name "unconnected-(U1-PWM2{slash}GPMI_RDY3-Pad91)") (class "Default")
      (node (ref "U1") (pin "91") (pinfunction "PWM2/GPMI_RDY3_91") (pintype "bidirectional"))
    )
    (net (code "129") (name "unconnected-(U1-SSP1_DETECT{slash}GPMI_CE3N{slash}USB_ID-Pad88)") (class "Default")
      (node (ref "U1") (pin "88") (pinfunction "SSP1_DETECT/GPMI_CE3N/USB_ID_88") (pintype "bidirectional"))
    )
    (net (code "130") (name "unconnected-(U1-VDAC1-Pad104)") (class "Default")
      (node (ref "U1") (pin "104") (pinfunction "VDAC1_104") (pintype "output"))
    )
    (net (code "131") (name "unconnected-(U2-NC1-Pad14)") (class "Default")
      (node (ref "U2") (pin "14") (pinfunction "NC1_14") (pintype "no_connect"))
    )
    (net (code "132") (name "unconnected-(U2-NC2-Pad17)") (class "Default")
      (node (ref "U2") (pin "17") (pinfunction "NC2_17") (pintype "no_connect"))
    )
    (net (code "133") (name "unconnected-(U2-NC3-Pad19)") (class "Default")
      (node (ref "U2") (pin "19") (pinfunction "NC3_19") (pintype "no_connect"))
    )
    (net (code "134") (name "unconnected-(U2-NC4-Pad25)") (class "Default")
      (node (ref "U2") (pin "25") (pinfunction "NC4_25") (pintype "no_connect"))
    )
    (net (code "135") (name "unconnected-(U2-NC5-Pad43)") (class "Default")
      (node (ref "U2") (pin "43") (pinfunction "NC5_43") (pintype "no_connect"))
    )
    (net (code "136") (name "unconnected-(U2-NC6-Pad50)") (class "Default")
      (node (ref "U2") (pin "50") (pinfunction "NC6_50") (pintype "no_connect"))
    )
    (net (code "137") (name "unconnected-(U2-NC7-Pad53)") (class "Default")
      (node (ref "U2") (pin "53") (pinfunction "NC7_53") (pintype "no_connect"))
    )
    (net (code "138") (name "unconnected-(U3-NC-Pad1)") (class "Default")
      (node (ref "U3") (pin "1") (pinfunction "NC_1") (pintype "no_connect"))
    )
    (net (code "139") (name "unconnected-(U3-NC-Pad2)") (class "Default")
      (node (ref "U3") (pin "2") (pinfunction "NC_2") (pintype "no_connect"))
    )
    (net (code "140") (name "unconnected-(U3-NC-Pad3)") (class "Default")
      (node (ref "U3") (pin "3") (pinfunction "NC_3") (pintype "no_connect"))
    )
    (net (code "141") (name "unconnected-(U3-NC-Pad4)") (class "Default")
      (node (ref "U3") (pin "4") (pinfunction "NC_4") (pintype "no_connect"))
    )
    (net (code "142") (name "unconnected-(U3-NC-Pad5)") (class "Default")
      (node (ref "U3") (pin "5") (pinfunction "NC_5") (pintype "no_connect"))
    )
    (net (code "143") (name "unconnected-(U3-NC-Pad6)") (class "Default")
      (node (ref "U3") (pin "6") (pinfunction "NC_6") (pintype "no_connect"))
    )
    (net (code "144") (name "unconnected-(U3-NC-Pad10)") (class "Default")
      (node (ref "U3") (pin "10") (pinfunction "NC_10") (pintype "no_connect"))
    )
    (net (code "145") (name "unconnected-(U3-NC-Pad11)") (class "Default")
      (node (ref "U3") (pin "11") (pinfunction "NC_11") (pintype "no_connect"))
    )
    (net (code "146") (name "unconnected-(U3-NC-Pad14)") (class "Default")
      (node (ref "U3") (pin "14") (pinfunction "NC_14") (pintype "no_connect"))
    )
    (net (code "147") (name "unconnected-(U3-NC-Pad15)") (class "Default")
      (node (ref "U3") (pin "15") (pinfunction "NC_15") (pintype "no_connect"))
    )
    (net (code "148") (name "unconnected-(U3-NC-Pad20)") (class "Default")
      (node (ref "U3") (pin "20") (pinfunction "NC_20") (pintype "no_connect"))
    )
    (net (code "149") (name "unconnected-(U3-NC-Pad21)") (class "Default")
      (node (ref "U3") (pin "21") (pinfunction "NC_21") (pintype "no_connect"))
    )
    (net (code "150") (name "unconnected-(U3-NC-Pad22)") (class "Default")
      (node (ref "U3") (pin "22") (pinfunction "NC_22") (pintype "no_connect"))
    )
    (net (code "151") (name "unconnected-(U3-NC-Pad23)") (class "Default")
      (node (ref "U3") (pin "23") (pinfunction "NC_23") (pintype "no_connect"))
    )
    (net (code "152") (name "unconnected-(U3-NC-Pad24)") (class "Default")
      (node (ref "U3") (pin "24") (pinfunction "NC_24") (pintype "no_connect"))
    )
    (net (code "153") (name "unconnected-(U3-NC-Pad25)") (class "Default")
      (node (ref "U3") (pin "25") (pinfunction "NC_25") (pintype "no_connect"))
    )
    (net (code "154") (name "unconnected-(U3-NC-Pad26)") (class "Default")
      (node (ref "U3") (pin "26") (pinfunction "NC_26") (pintype "no_connect"))
    )
    (net (code "155") (name "unconnected-(U3-NC-Pad27)") (class "Default")
      (node (ref "U3") (pin "27") (pinfunction "NC_27") (pintype "no_connect"))
    )
    (net (code "156") (name "unconnected-(U3-NC-Pad28)") (class "Default")
      (node (ref "U3") (pin "28") (pinfunction "NC_28") (pintype "no_connect"))
    )
    (net (code "157") (name "unconnected-(U3-NC-Pad33)") (class "Default")
      (node (ref "U3") (pin "33") (pinfunction "NC_33") (pintype "no_connect"))
    )
    (net (code "158") (name "unconnected-(U3-NC-Pad34)") (class "Default")
      (node (ref "U3") (pin "34") (pinfunction "NC_34") (pintype "no_connect"))
    )
    (net (code "159") (name "unconnected-(U3-NC-Pad35)") (class "Default")
      (node (ref "U3") (pin "35") (pinfunction "NC_35") (pintype "no_connect"))
    )
    (net (code "160") (name "unconnected-(U3-NC-Pad38)") (class "Default")
      (node (ref "U3") (pin "38") (pinfunction "NC_38") (pintype "no_connect"))
    )
    (net (code "161") (name "unconnected-(U3-NC-Pad39)") (class "Default")
      (node (ref "U3") (pin "39") (pinfunction "NC_39") (pintype "no_connect"))
    )
    (net (code "162") (name "unconnected-(U3-NC-Pad40)") (class "Default")
      (node (ref "U3") (pin "40") (pinfunction "NC_40") (pintype "no_connect"))
    )
    (net (code "163") (name "unconnected-(U3-NC-Pad45)") (class "Default")
      (node (ref "U3") (pin "45") (pinfunction "NC_45") (pintype "no_connect"))
    )
    (net (code "164") (name "unconnected-(U3-NC-Pad46)") (class "Default")
      (node (ref "U3") (pin "46") (pinfunction "NC_46") (pintype "no_connect"))
    )
    (net (code "165") (name "unconnected-(U3-NC-Pad47)") (class "Default")
      (node (ref "U3") (pin "47") (pinfunction "NC_47") (pintype "no_connect"))
    )
    (net (code "166") (name "unconnected-(U3-NC-Pad48)") (class "Default")
      (node (ref "U3") (pin "48") (pinfunction "NC_48") (pintype "no_connect"))
    )
  )
)
